# SPosition.net
KiCad netlist of a schematic drawn in EAGLE
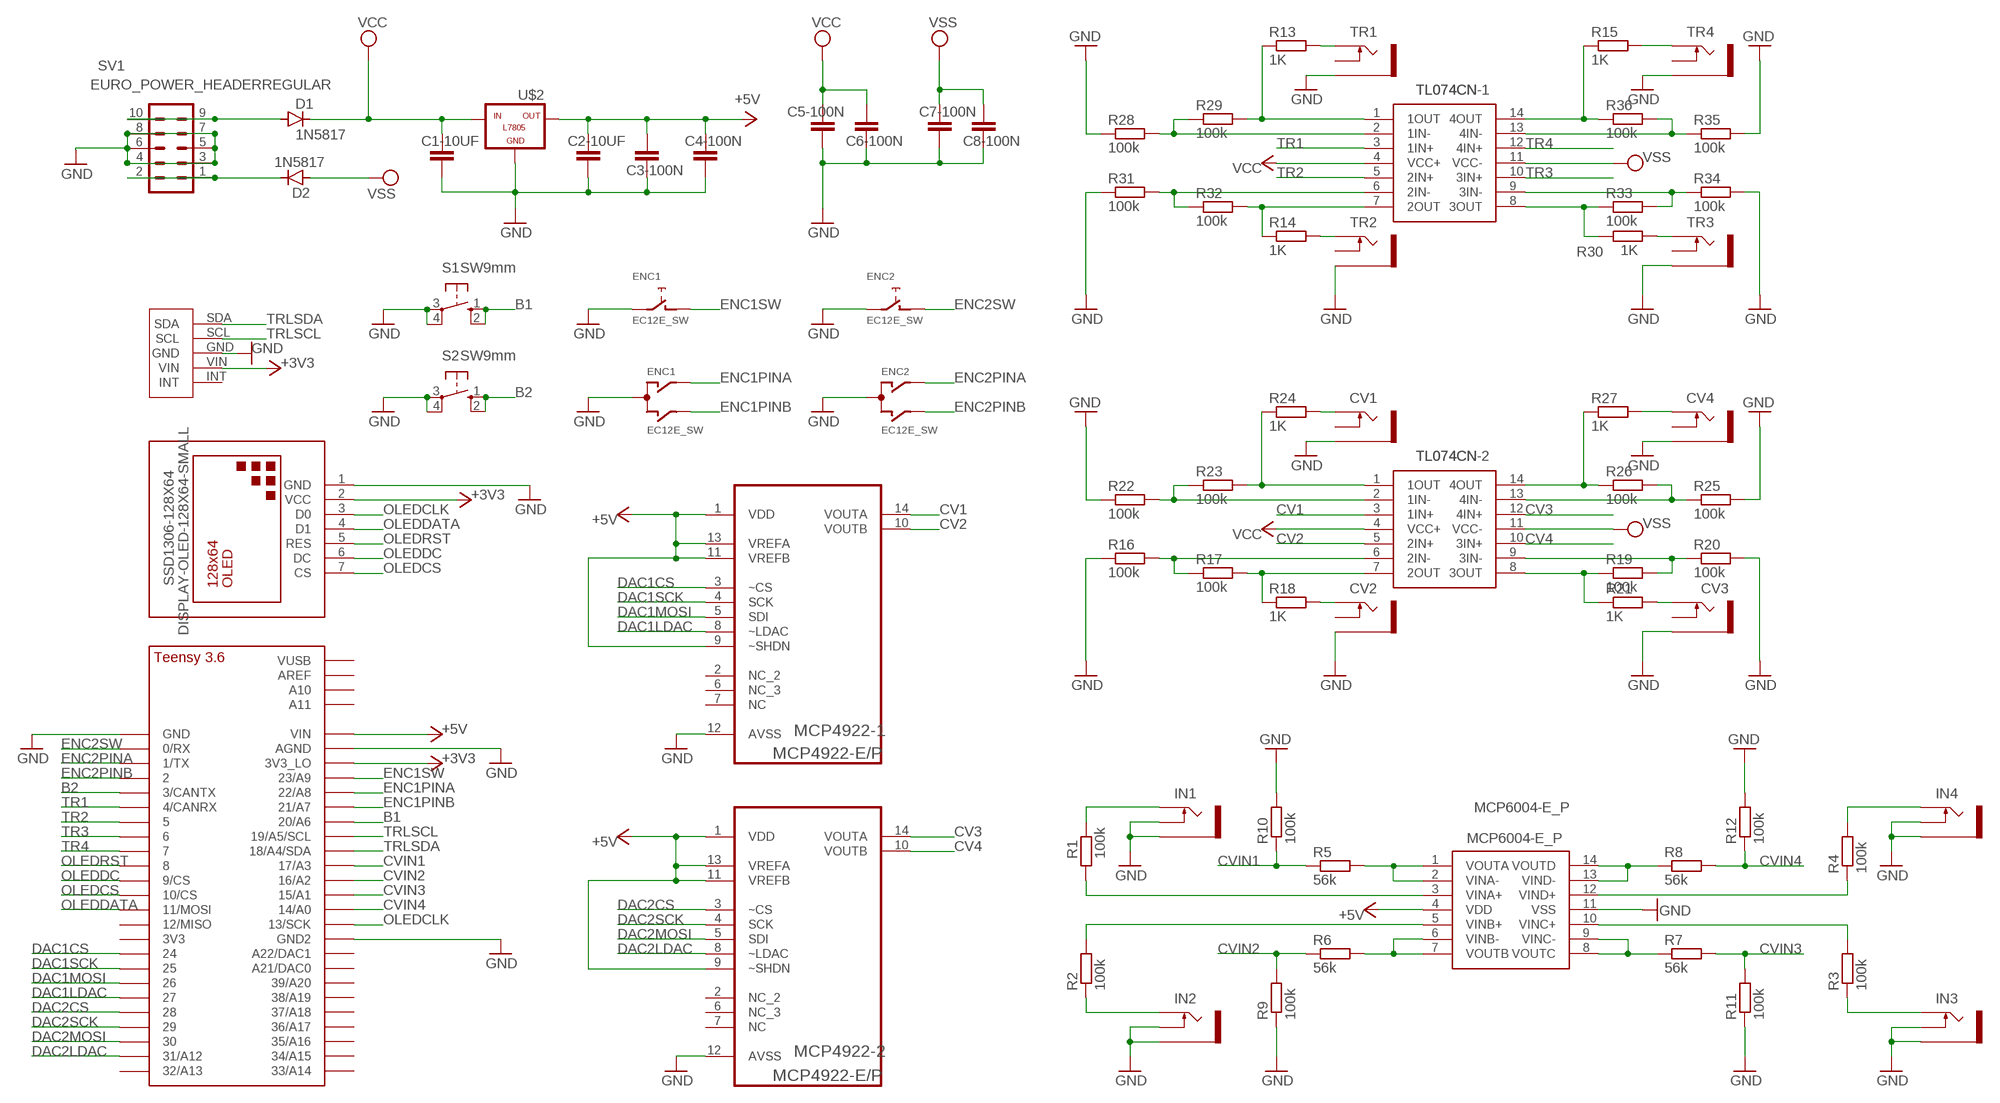
[diagram p0: schematic, sheet 1]

(export (version "E")
  (design (tool "Eeschema 10.0.6"))
  (components
    (comp (ref "C1-10UF")
      (value "10uF")
      (footprint "eagle-import:C0805")
      (libsource (lib "eagle-import") (part "C-EUC0805"))
    )
    (comp (ref "C2-10UF")
      (value "10uF")
      (footprint "eagle-import:C0805")
      (libsource (lib "eagle-import") (part "C-EUC0805"))
    )
    (comp (ref "C3-100N")
      (value "100n")
      (footprint "eagle-import:C0805")
      (libsource (lib "eagle-import") (part "C-EUC0805"))
    )
    (comp (ref "C4-100N")
      (value "100n")
      (footprint "eagle-import:C0805")
      (libsource (lib "eagle-import") (part "C-EUC0805"))
    )
    (comp (ref "C5-100N")
      (value "100n")
      (footprint "eagle-import:C0805")
      (libsource (lib "eagle-import") (part "C-EUC0805"))
    )
    (comp (ref "C6-100N")
      (value "100n")
      (footprint "eagle-import:C0805")
      (libsource (lib "eagle-import") (part "C-EUC0805"))
    )
    (comp (ref "C7-100N")
      (value "100n")
      (footprint "eagle-import:C0805")
      (libsource (lib "eagle-import") (part "C-EUC0805"))
    )
    (comp (ref "C8-100N")
      (value "100n")
      (footprint "eagle-import:C0805")
      (libsource (lib "eagle-import") (part "C-EUC0805"))
    )
    (comp (ref "CV1")
      (value "THONKICONNNEW")
      (footprint "eagle-import:WQP-PJ301M-12_JACK")
      (libsource (lib "eagle-import") (part "THONKICONNNEW"))
    )
    (comp (ref "CV2")
      (value "THONKICONNNEW")
      (footprint "eagle-import:WQP-PJ301M-12_JACK")
      (libsource (lib "eagle-import") (part "THONKICONNNEW"))
    )
    (comp (ref "CV3")
      (value "THONKICONNNEW")
      (footprint "eagle-import:WQP-PJ301M-12_JACK")
      (libsource (lib "eagle-import") (part "THONKICONNNEW"))
    )
    (comp (ref "CV4")
      (value "THONKICONNNEW")
      (footprint "eagle-import:WQP-PJ301M-12_JACK")
      (libsource (lib "eagle-import") (part "THONKICONNNEW"))
    )
    (comp (ref "D1")
      (value "1N5817")
      (footprint "eagle-import:DO41-10")
      (libsource (lib "eagle-import") (part "1N4004"))
    )
    (comp (ref "D2")
      (value "1N5817")
      (footprint "eagle-import:DO41-10")
      (libsource (lib "eagle-import") (part "1N4004"))
    )
    (comp (ref "ENC1")
      (value "EC12E_SW")
      (footprint "eagle-import:ALPS_EC12E_SW")
      (fields (field (name "MPN") "EC12E2424407"))
      (libsource (lib "eagle-import") (part "EC12E_SW"))
    )
    (comp (ref "ENC2")
      (value "EC12E_SW")
      (footprint "eagle-import:ALPS_EC12E_SW")
      (fields (field (name "MPN") "EC12E2424407"))
      (libsource (lib "eagle-import") (part "EC12E_SW"))
    )
    (comp (ref "IN1")
      (value "THONKICONNNEW")
      (footprint "eagle-import:WQP-PJ301M-12_JACK")
      (libsource (lib "eagle-import") (part "THONKICONNNEW"))
    )
    (comp (ref "IN2")
      (value "THONKICONNNEW")
      (footprint "eagle-import:WQP-PJ301M-12_JACK")
      (libsource (lib "eagle-import") (part "THONKICONNNEW"))
    )
    (comp (ref "IN3")
      (value "THONKICONNNEW")
      (footprint "eagle-import:WQP-PJ301M-12_JACK")
      (libsource (lib "eagle-import") (part "THONKICONNNEW"))
    )
    (comp (ref "IN4")
      (value "THONKICONNNEW")
      (footprint "eagle-import:WQP-PJ301M-12_JACK")
      (libsource (lib "eagle-import") (part "THONKICONNNEW"))
    )
    (comp (ref "MCP4922-1")
      (value "MCP4922-E/P")
      (footprint "eagle-import:DIP254P762X533-14")
      (fields (field (name "MF") "Microchip"))
      (libsource (lib "eagle-import") (part "MCP4922-E/P"))
    )
    (comp (ref "MCP4922-2")
      (value "MCP4922-E/P")
      (footprint "eagle-import:DIP254P762X533-14")
      (fields (field (name "MF") "Microchip"))
      (libsource (lib "eagle-import") (part "MCP4922-E/P"))
    )
    (comp (ref "MCP6004-E_P")
      (value "MCP6004-E_P")
      (footprint "eagle-import:DIP781W56P254L1918H533Q14N")
      (fields
        (field (name "MANUFACTURER_PART_NUMBER") "mcp6004-e/p")
        (field (name "MOUSER_PART_NUMBER") "579-MCP6004-E/P")
        (field (name "RS_PART_NUMBER") "7386178P")
      )
      (libsource (lib "eagle-import") (part "MCP6004-E_P"))
    )
    (comp (ref "R1")
      (value "100k")
      (footprint "eagle-import:R0805")
      (libsource (lib "eagle-import") (part "R-EU_R0805"))
    )
    (comp (ref "R2")
      (value "100k")
      (footprint "eagle-import:R0805")
      (libsource (lib "eagle-import") (part "R-EU_R0805"))
    )
    (comp (ref "R3")
      (value "100k")
      (footprint "eagle-import:R0805")
      (libsource (lib "eagle-import") (part "R-EU_R0805"))
    )
    (comp (ref "R4")
      (value "100k")
      (footprint "eagle-import:R0805")
      (libsource (lib "eagle-import") (part "R-EU_R0805"))
    )
    (comp (ref "R5")
      (value "56k")
      (footprint "eagle-import:R0805")
      (libsource (lib "eagle-import") (part "R-EU_R0805"))
    )
    (comp (ref "R6")
      (value "56k")
      (footprint "eagle-import:R0805")
      (libsource (lib "eagle-import") (part "R-EU_R0805"))
    )
    (comp (ref "R7")
      (value "56k")
      (footprint "eagle-import:R0805")
      (libsource (lib "eagle-import") (part "R-EU_R0805"))
    )
    (comp (ref "R8")
      (value "56k")
      (footprint "eagle-import:R0805")
      (libsource (lib "eagle-import") (part "R-EU_R0805"))
    )
    (comp (ref "R9")
      (value "100k")
      (footprint "eagle-import:R0805")
      (libsource (lib "eagle-import") (part "R-EU_R0805"))
    )
    (comp (ref "R10")
      (value "100k")
      (footprint "eagle-import:R0805")
      (libsource (lib "eagle-import") (part "R-EU_R0805"))
    )
    (comp (ref "R11")
      (value "100k")
      (footprint "eagle-import:R0805")
      (libsource (lib "eagle-import") (part "R-EU_R0805"))
    )
    (comp (ref "R12")
      (value "100k")
      (footprint "eagle-import:R0805")
      (libsource (lib "eagle-import") (part "R-EU_R0805"))
    )
    (comp (ref "R13")
      (value "1K")
      (footprint "eagle-import:R0805")
      (libsource (lib "eagle-import") (part "R-EU_R0805"))
    )
    (comp (ref "R14")
      (value "1K")
      (footprint "eagle-import:R0805")
      (libsource (lib "eagle-import") (part "R-EU_R0805"))
    )
    (comp (ref "R15")
      (value "1K")
      (footprint "eagle-import:R0805")
      (libsource (lib "eagle-import") (part "R-EU_R0805"))
    )
    (comp (ref "R16")
      (value "100k")
      (footprint "eagle-import:R0805")
      (libsource (lib "eagle-import") (part "R-EU_R0805"))
    )
    (comp (ref "R17")
      (value "100k")
      (footprint "eagle-import:R0805")
      (libsource (lib "eagle-import") (part "R-EU_R0805"))
    )
    (comp (ref "R18")
      (value "1K")
      (footprint "eagle-import:R0805")
      (libsource (lib "eagle-import") (part "R-EU_R0805"))
    )
    (comp (ref "R19")
      (value "100k")
      (footprint "eagle-import:R0805")
      (libsource (lib "eagle-import") (part "R-EU_R0805"))
    )
    (comp (ref "R20")
      (value "100k")
      (footprint "eagle-import:R0805")
      (libsource (lib "eagle-import") (part "R-EU_R0805"))
    )
    (comp (ref "R21")
      (value "1K")
      (footprint "eagle-import:R0805")
      (libsource (lib "eagle-import") (part "R-EU_R0805"))
    )
    (comp (ref "R22")
      (value "100k")
      (footprint "eagle-import:R0805")
      (libsource (lib "eagle-import") (part "R-EU_R0805"))
    )
    (comp (ref "R23")
      (value "100k")
      (footprint "eagle-import:R0805")
      (libsource (lib "eagle-import") (part "R-EU_R0805"))
    )
    (comp (ref "R24")
      (value "1K")
      (footprint "eagle-import:R0805")
      (libsource (lib "eagle-import") (part "R-EU_R0805"))
    )
    (comp (ref "R25")
      (value "100k")
      (footprint "eagle-import:R0805")
      (libsource (lib "eagle-import") (part "R-EU_R0805"))
    )
    (comp (ref "R26")
      (value "100k")
      (footprint "eagle-import:R0805")
      (libsource (lib "eagle-import") (part "R-EU_R0805"))
    )
    (comp (ref "R27")
      (value "1K")
      (footprint "eagle-import:R0805")
      (libsource (lib "eagle-import") (part "R-EU_R0805"))
    )
    (comp (ref "R28")
      (value "100k")
      (footprint "eagle-import:R0805")
      (libsource (lib "eagle-import") (part "R-EU_R0805"))
    )
    (comp (ref "R29")
      (value "100k")
      (footprint "eagle-import:R0805")
      (libsource (lib "eagle-import") (part "R-EU_R0805"))
    )
    (comp (ref "R30")
      (value "1K")
      (footprint "eagle-import:R0805")
      (libsource (lib "eagle-import") (part "R-EU_R0805"))
    )
    (comp (ref "R31")
      (value "100k")
      (footprint "eagle-import:R0805")
      (libsource (lib "eagle-import") (part "R-EU_R0805"))
    )
    (comp (ref "R32")
      (value "100k")
      (footprint "eagle-import:R0805")
      (libsource (lib "eagle-import") (part "R-EU_R0805"))
    )
    (comp (ref "R33")
      (value "100k")
      (footprint "eagle-import:R0805")
      (libsource (lib "eagle-import") (part "R-EU_R0805"))
    )
    (comp (ref "R34")
      (value "100k")
      (footprint "eagle-import:R0805")
      (libsource (lib "eagle-import") (part "R-EU_R0805"))
    )
    (comp (ref "R35")
      (value "100k")
      (footprint "eagle-import:R0805")
      (libsource (lib "eagle-import") (part "R-EU_R0805"))
    )
    (comp (ref "R36")
      (value "100k")
      (footprint "eagle-import:R0805")
      (libsource (lib "eagle-import") (part "R-EU_R0805"))
    )
    (comp (ref "S1")
      (value "SW9mm")
      (footprint "eagle-import:B3F-10XX")
      (fields (field (name "MPN") "B3F-1000"))
      (libsource (lib "eagle-import") (part "10-XX"))
    )
    (comp (ref "S2")
      (value "SW9mm")
      (footprint "eagle-import:B3F-10XX")
      (fields (field (name "MPN") "B3F-1000"))
      (libsource (lib "eagle-import") (part "10-XX"))
    )
    (comp (ref "SSD1306-128X64")
      (value "DISPLAY-OLED-128X64-SMALL")
      (footprint "eagle-import:DISPLAY-OLED-128X64-SMALL")
      (libsource (lib "eagle-import") (part "DISPLAY-OLED-128X64-SMALL"))
    )
    (comp (ref "SV1")
      (value "EURO_POWER_HEADERREGULAR")
      (footprint "eagle-import:EURO_POWER_HEADER")
      (libsource (lib "eagle-import") (part "EURO_POWER_HEADERREGULAR"))
    )
    (comp (ref "TL074CN-1")
      (value "TL074CN")
      (footprint "eagle-import:DIP794W53P254L1930H508Q14N")
      (fields (field (name "MOUSER_PART_NUMBER") "595-TL074CN") (field (name "RS_PART_NUMBER") "0302621P"))
      (libsource (lib "eagle-import") (part "TL074CN"))
    )
    (comp (ref "TL074CN-2")
      (value "TL074CN")
      (footprint "eagle-import:DIP794W53P254L1930H508Q14N")
      (fields (field (name "MOUSER_PART_NUMBER") "595-TL074CN") (field (name "RS_PART_NUMBER") "0302621P"))
      (libsource (lib "eagle-import") (part "TL074CN"))
    )
    (comp (ref "TR1")
      (value "THONKICONNNEW")
      (footprint "eagle-import:WQP-PJ301M-12_JACK")
      (libsource (lib "eagle-import") (part "THONKICONNNEW"))
    )
    (comp (ref "TR2")
      (value "THONKICONNNEW")
      (footprint "eagle-import:WQP-PJ301M-12_JACK")
      (libsource (lib "eagle-import") (part "THONKICONNNEW"))
    )
    (comp (ref "TR3")
      (value "THONKICONNNEW")
      (footprint "eagle-import:WQP-PJ301M-12_JACK")
      (libsource (lib "eagle-import") (part "THONKICONNNEW"))
    )
    (comp (ref "TR4")
      (value "THONKICONNNEW")
      (footprint "eagle-import:WQP-PJ301M-12_JACK")
      (libsource (lib "eagle-import") (part "THONKICONNNEW"))
    )
    (comp (ref "U$1")
      (value "TEENSY_3.5/3.6_BASIC")
      (footprint "eagle-import:TEENSY_3.5_3.6_BASIC")
      (libsource (lib "eagle-import") (part "TEENSY_3.5/3.6_BASIC"))
    )
    (comp (ref "U$2")
      (value "-L7805")
      (footprint "eagle-import:L7805")
      (libsource (lib "eagle-import") (part "-L7805"))
    )
    (comp (ref "U$4")
      (value "SPREV5")
      (footprint "eagle-import:SPREV5")
      (libsource (lib "eagle-import") (part "SPREV5"))
    )
  )
  (nets
    (net (code "1") (name "+3V3") (class "Default")
      (node (ref "SSD1306-128X64") (pin "2") (pinfunction "VCC_2") (pintype "power_in"))
      (node (ref "U$1") (pin "3V3_LO") (pinfunction "3V3_LO_3V3_LO") (pintype "bidirectional"))
      (node (ref "U$4") (pin "VIN") (pinfunction "VIN_VIN") (pintype "bidirectional"))
    )
    (net (code "2") (name "+5V") (class "Default")
      (node (ref "C2-10UF") (pin "1") (pinfunction "1_1") (pintype "passive"))
      (node (ref "C3-100N") (pin "1") (pinfunction "1_1") (pintype "passive"))
      (node (ref "C4-100N") (pin "1") (pinfunction "1_1") (pintype "passive"))
      (node (ref "MCP4922-1") (pin "1") (pinfunction "VDD_1") (pintype "power_in"))
      (node (ref "MCP4922-1") (pin "11") (pinfunction "VREFB_11") (pintype "input"))
      (node (ref "MCP4922-1") (pin "13") (pinfunction "VREFA_13") (pintype "input"))
      (node (ref "MCP4922-1") (pin "9") (pinfunction "~{SHDN}_9") (pintype "input"))
      (node (ref "MCP4922-2") (pin "1") (pinfunction "VDD_1") (pintype "power_in"))
      (node (ref "MCP4922-2") (pin "11") (pinfunction "VREFB_11") (pintype "input"))
      (node (ref "MCP4922-2") (pin "13") (pinfunction "VREFA_13") (pintype "input"))
      (node (ref "MCP4922-2") (pin "9") (pinfunction "~{SHDN}_9") (pintype "input"))
      (node (ref "MCP6004-E_P") (pin "4") (pinfunction "VDD_4") (pintype "power_in"))
      (node (ref "U$1") (pin "VIN") (pinfunction "VIN_VIN") (pintype "bidirectional"))
      (node (ref "U$2") (pin "OUT") (pinfunction "OUT_OUT") (pintype "passive"))
    )
    (net (code "3") (name "/B1") (class "Default")
      (node (ref "S1") (pin "1") (pinfunction "S_1") (pintype "passive"))
      (node (ref "S1") (pin "2") (pinfunction "S1_2") (pintype "passive"))
      (node (ref "U$1") (pin "20/A6") (pinfunction "20/A6_20/A6") (pintype "bidirectional"))
    )
    (net (code "4") (name "/B2") (class "Default")
      (node (ref "S2") (pin "1") (pinfunction "S_1") (pintype "passive"))
      (node (ref "S2") (pin "2") (pinfunction "S1_2") (pintype "passive"))
      (node (ref "U$1") (pin "3/CANTX") (pinfunction "3/CANTX_3/CANTX") (pintype "bidirectional"))
    )
    (net (code "5") (name "/CV1") (class "Default")
      (node (ref "MCP4922-1") (pin "14") (pinfunction "VOUTA_14") (pintype "output"))
      (node (ref "TL074CN-2") (pin "3") (pinfunction "1IN+_3") (pintype "input"))
    )
    (net (code "6") (name "/CV2") (class "Default")
      (node (ref "MCP4922-1") (pin "10") (pinfunction "VOUTB_10") (pintype "output"))
      (node (ref "TL074CN-2") (pin "5") (pinfunction "2IN+_5") (pintype "input"))
    )
    (net (code "7") (name "/CV3") (class "Default")
      (node (ref "MCP4922-2") (pin "14") (pinfunction "VOUTA_14") (pintype "output"))
      (node (ref "TL074CN-2") (pin "12") (pinfunction "4IN+_12") (pintype "input"))
    )
    (net (code "8") (name "/CV4") (class "Default")
      (node (ref "MCP4922-2") (pin "10") (pinfunction "VOUTB_10") (pintype "output"))
      (node (ref "TL074CN-2") (pin "10") (pinfunction "3IN+_10") (pintype "input"))
    )
    (net (code "9") (name "/CVIN1") (class "Default")
      (node (ref "R10") (pin "1") (pinfunction "1_1") (pintype "passive"))
      (node (ref "R5") (pin "1") (pinfunction "1_1") (pintype "passive"))
      (node (ref "U$1") (pin "17/A3") (pinfunction "17/A3_17/A3") (pintype "bidirectional"))
    )
    (net (code "10") (name "/CVIN2") (class "Default")
      (node (ref "R6") (pin "1") (pinfunction "1_1") (pintype "passive"))
      (node (ref "R9") (pin "2") (pinfunction "2_2") (pintype "passive"))
      (node (ref "U$1") (pin "16/A2") (pinfunction "16/A2_16/A2") (pintype "bidirectional"))
    )
    (net (code "11") (name "/CVIN3") (class "Default")
      (node (ref "R11") (pin "2") (pinfunction "2_2") (pintype "passive"))
      (node (ref "R7") (pin "2") (pinfunction "2_2") (pintype "passive"))
      (node (ref "U$1") (pin "15/A1") (pinfunction "15/A1_15/A1") (pintype "bidirectional"))
    )
    (net (code "12") (name "/CVIN4") (class "Default")
      (node (ref "R12") (pin "1") (pinfunction "1_1") (pintype "passive"))
      (node (ref "R8") (pin "2") (pinfunction "2_2") (pintype "passive"))
      (node (ref "U$1") (pin "14/A0") (pinfunction "14/A0_14/A0") (pintype "bidirectional"))
    )
    (net (code "13") (name "/DAC1CS") (class "Default")
      (node (ref "MCP4922-1") (pin "3") (pinfunction "~{CS}_3") (pintype "input"))
      (node (ref "U$1") (pin "24") (pinfunction "24_24") (pintype "bidirectional"))
    )
    (net (code "14") (name "/DAC1LDAC") (class "Default")
      (node (ref "MCP4922-1") (pin "8") (pinfunction "~{LDAC}_8") (pintype "input"))
      (node (ref "U$1") (pin "27") (pinfunction "27_27") (pintype "bidirectional"))
    )
    (net (code "15") (name "/DAC1MOSI") (class "Default")
      (node (ref "MCP4922-1") (pin "5") (pinfunction "SDI_5") (pintype "input"))
      (node (ref "U$1") (pin "26") (pinfunction "26_26") (pintype "bidirectional"))
    )
    (net (code "16") (name "/DAC1SCK") (class "Default")
      (node (ref "MCP4922-1") (pin "4") (pinfunction "SCK_4") (pintype "input"))
      (node (ref "U$1") (pin "25") (pinfunction "25_25") (pintype "bidirectional"))
    )
    (net (code "17") (name "/DAC2CS") (class "Default")
      (node (ref "MCP4922-2") (pin "3") (pinfunction "~{CS}_3") (pintype "input"))
      (node (ref "U$1") (pin "28") (pinfunction "28_28") (pintype "bidirectional"))
    )
    (net (code "18") (name "/DAC2LDAC") (class "Default")
      (node (ref "MCP4922-2") (pin "8") (pinfunction "~{LDAC}_8") (pintype "input"))
      (node (ref "U$1") (pin "31/A12") (pinfunction "31/A12_31/A12") (pintype "bidirectional"))
    )
    (net (code "19") (name "/DAC2MOSI") (class "Default")
      (node (ref "MCP4922-2") (pin "5") (pinfunction "SDI_5") (pintype "input"))
      (node (ref "U$1") (pin "30") (pinfunction "30_30") (pintype "bidirectional"))
    )
    (net (code "20") (name "/DAC2SCK") (class "Default")
      (node (ref "MCP4922-2") (pin "4") (pinfunction "SCK_4") (pintype "input"))
      (node (ref "U$1") (pin "29") (pinfunction "29_29") (pintype "bidirectional"))
    )
    (net (code "21") (name "/ENC1PINA") (class "Default")
      (node (ref "ENC1") (pin "A") (pinfunction "A_A") (pintype "passive"))
      (node (ref "U$1") (pin "22/A8") (pinfunction "22/A8_22/A8") (pintype "bidirectional"))
    )
    (net (code "22") (name "/ENC1PINB") (class "Default")
      (node (ref "ENC1") (pin "B") (pinfunction "B_B") (pintype "passive"))
      (node (ref "U$1") (pin "21/A7") (pinfunction "21/A7_21/A7") (pintype "bidirectional"))
    )
    (net (code "23") (name "/ENC1SW") (class "Default")
      (node (ref "ENC1") (pin "D") (pinfunction "1_D") (pintype "passive"))
      (node (ref "U$1") (pin "23/A9") (pinfunction "23/A9_23/A9") (pintype "bidirectional"))
    )
    (net (code "24") (name "/ENC2PINA") (class "Default")
      (node (ref "ENC2") (pin "A") (pinfunction "A_A") (pintype "passive"))
      (node (ref "U$1") (pin "1/TX") (pinfunction "1/TX_1/TX") (pintype "bidirectional"))
    )
    (net (code "25") (name "/ENC2PINB") (class "Default")
      (node (ref "ENC2") (pin "B") (pinfunction "B_B") (pintype "passive"))
      (node (ref "U$1") (pin "2") (pinfunction "2_2") (pintype "bidirectional"))
    )
    (net (code "26") (name "/ENC2SW") (class "Default")
      (node (ref "ENC2") (pin "D") (pinfunction "1_D") (pintype "passive"))
      (node (ref "U$1") (pin "0/RX") (pinfunction "0/RX_0/RX") (pintype "bidirectional"))
    )
    (net (code "27") (name "/OLEDCLK") (class "Default")
      (node (ref "SSD1306-128X64") (pin "3") (pinfunction "D0_3") (pintype "bidirectional"))
      (node (ref "U$1") (pin "13/SCK") (pinfunction "13/SCK_13/SCK") (pintype "bidirectional"))
    )
    (net (code "28") (name "/OLEDCS") (class "Default")
      (node (ref "SSD1306-128X64") (pin "7") (pinfunction "CS_7") (pintype "bidirectional"))
      (node (ref "U$1") (pin "10/CS") (pinfunction "10/CS_10/CS") (pintype "bidirectional"))
    )
    (net (code "29") (name "/OLEDDATA") (class "Default")
      (node (ref "SSD1306-128X64") (pin "4") (pinfunction "D1_4") (pintype "bidirectional"))
      (node (ref "U$1") (pin "11/MOSI") (pinfunction "11/MOSI_11/MOSI") (pintype "bidirectional"))
    )
    (net (code "30") (name "/OLEDDC") (class "Default")
      (node (ref "SSD1306-128X64") (pin "6") (pinfunction "DC_6") (pintype "bidirectional"))
      (node (ref "U$1") (pin "9/CS") (pinfunction "9/CS_9/CS") (pintype "bidirectional"))
    )
    (net (code "31") (name "/OLEDRST") (class "Default")
      (node (ref "SSD1306-128X64") (pin "5") (pinfunction "RES_5") (pintype "bidirectional"))
      (node (ref "U$1") (pin "8") (pinfunction "8_8") (pintype "bidirectional"))
    )
    (net (code "32") (name "/TR1") (class "Default")
      (node (ref "TL074CN-1") (pin "3") (pinfunction "1IN+_3") (pintype "input"))
      (node (ref "U$1") (pin "4/CANRX") (pinfunction "4/CANRX_4/CANRX") (pintype "bidirectional"))
    )
    (net (code "33") (name "/TR2") (class "Default")
      (node (ref "TL074CN-1") (pin "5") (pinfunction "2IN+_5") (pintype "input"))
      (node (ref "U$1") (pin "5") (pinfunction "5_5") (pintype "bidirectional"))
    )
    (net (code "34") (name "/TR3") (class "Default")
      (node (ref "TL074CN-1") (pin "10") (pinfunction "3IN+_10") (pintype "input"))
      (node (ref "U$1") (pin "6") (pinfunction "6_6") (pintype "bidirectional"))
    )
    (net (code "35") (name "/TR4") (class "Default")
      (node (ref "TL074CN-1") (pin "12") (pinfunction "4IN+_12") (pintype "input"))
      (node (ref "U$1") (pin "7") (pinfunction "7_7") (pintype "bidirectional"))
    )
    (net (code "36") (name "/TRLSCL") (class "Default")
      (node (ref "U$1") (pin "19/A5/SCL") (pinfunction "19/A5/SCL_19/A5/SCL") (pintype "bidirectional"))
      (node (ref "U$4") (pin "SCL") (pinfunction "SCL_SCL") (pintype "bidirectional"))
    )
    (net (code "37") (name "/TRLSDA") (class "Default")
      (node (ref "U$1") (pin "18/A4/SDA") (pinfunction "18/A4/SDA_18/A4/SDA") (pintype "bidirectional"))
      (node (ref "U$4") (pin "SDA") (pinfunction "SDA_SDA") (pintype "bidirectional"))
    )
    (net (code "38") (name "GND") (class "Default")
      (node (ref "C1-10UF") (pin "2") (pinfunction "2_2") (pintype "passive"))
      (node (ref "C2-10UF") (pin "2") (pinfunction "2_2") (pintype "passive"))
      (node (ref "C3-100N") (pin "2") (pinfunction "2_2") (pintype "passive"))
      (node (ref "C4-100N") (pin "2") (pinfunction "2_2") (pintype "passive"))
      (node (ref "C5-100N") (pin "2") (pinfunction "2_2") (pintype "passive"))
      (node (ref "C6-100N") (pin "2") (pinfunction "2_2") (pintype "passive"))
      (node (ref "C7-100N") (pin "2") (pinfunction "2_2") (pintype "passive"))
      (node (ref "C8-100N") (pin "2") (pinfunction "2_2") (pintype "passive"))
      (node (ref "CV1") (pin "P$3_SLEEVE") (pinfunction "SLEEVE_P$3_SLEEVE") (pintype "passive"))
      (node (ref "CV2") (pin "P$3_SLEEVE") (pinfunction "SLEEVE_P$3_SLEEVE") (pintype "passive"))
      (node (ref "CV3") (pin "P$3_SLEEVE") (pinfunction "SLEEVE_P$3_SLEEVE") (pintype "passive"))
      (node (ref "CV4") (pin "P$3_SLEEVE") (pinfunction "SLEEVE_P$3_SLEEVE") (pintype "passive"))
      (node (ref "ENC1") (pin "C") (pinfunction "C_C") (pintype "passive"))
      (node (ref "ENC1") (pin "E") (pinfunction "2_E") (pintype "passive"))
      (node (ref "ENC2") (pin "C") (pinfunction "C_C") (pintype "passive"))
      (node (ref "ENC2") (pin "E") (pinfunction "2_E") (pintype "passive"))
      (node (ref "IN1") (pin "P$2_SWITCH") (pinfunction "SWITCH_P$2_SWITCH") (pintype "passive"))
      (node (ref "IN1") (pin "P$3_SLEEVE") (pinfunction "SLEEVE_P$3_SLEEVE") (pintype "passive"))
      (node (ref "IN2") (pin "P$2_SWITCH") (pinfunction "SWITCH_P$2_SWITCH") (pintype "passive"))
      (node (ref "IN2") (pin "P$3_SLEEVE") (pinfunction "SLEEVE_P$3_SLEEVE") (pintype "passive"))
      (node (ref "IN3") (pin "P$2_SWITCH") (pinfunction "SWITCH_P$2_SWITCH") (pintype "passive"))
      (node (ref "IN3") (pin "P$3_SLEEVE") (pinfunction "SLEEVE_P$3_SLEEVE") (pintype "passive"))
      (node (ref "IN4") (pin "P$2_SWITCH") (pinfunction "SWITCH_P$2_SWITCH") (pintype "passive"))
      (node (ref "IN4") (pin "P$3_SLEEVE") (pinfunction "SLEEVE_P$3_SLEEVE") (pintype "passive"))
      (node (ref "MCP4922-1") (pin "12") (pinfunction "AVSS_12") (pintype "power_in"))
      (node (ref "MCP4922-2") (pin "12") (pinfunction "AVSS_12") (pintype "power_in"))
      (node (ref "MCP6004-E_P") (pin "11") (pinfunction "VSS_11") (pintype "power_in"))
      (node (ref "R10") (pin "2") (pinfunction "2_2") (pintype "passive"))
      (node (ref "R11") (pin "1") (pinfunction "1_1") (pintype "passive"))
      (node (ref "R12") (pin "2") (pinfunction "2_2") (pintype "passive"))
      (node (ref "R16") (pin "1") (pinfunction "1_1") (pintype "passive"))
      (node (ref "R20") (pin "2") (pinfunction "2_2") (pintype "passive"))
      (node (ref "R22") (pin "1") (pinfunction "1_1") (pintype "passive"))
      (node (ref "R25") (pin "2") (pinfunction "2_2") (pintype "passive"))
      (node (ref "R28") (pin "1") (pinfunction "1_1") (pintype "passive"))
      (node (ref "R31") (pin "1") (pinfunction "1_1") (pintype "passive"))
      (node (ref "R34") (pin "2") (pinfunction "2_2") (pintype "passive"))
      (node (ref "R35") (pin "2") (pinfunction "2_2") (pintype "passive"))
      (node (ref "R9") (pin "1") (pinfunction "1_1") (pintype "passive"))
      (node (ref "S1") (pin "3") (pinfunction "P_3") (pintype "passive"))
      (node (ref "S1") (pin "4") (pinfunction "P1_4") (pintype "passive"))
      (node (ref "S2") (pin "3") (pinfunction "P_3") (pintype "passive"))
      (node (ref "S2") (pin "4") (pinfunction "P1_4") (pintype "passive"))
      (node (ref "SSD1306-128X64") (pin "1") (pinfunction "GND_1") (pintype "power_in"))
      (node (ref "SV1") (pin "3") (pinfunction "3_3") (pintype "passive"))
      (node (ref "SV1") (pin "4") (pinfunction "4_4") (pintype "passive"))
      (node (ref "SV1") (pin "5") (pinfunction "5_5") (pintype "passive"))
      (node (ref "SV1") (pin "6") (pinfunction "6_6") (pintype "passive"))
      (node (ref "SV1") (pin "7") (pinfunction "7_7") (pintype "passive"))
      (node (ref "SV1") (pin "8") (pinfunction "8_8") (pintype "passive"))
      (node (ref "TR1") (pin "P$3_SLEEVE") (pinfunction "SLEEVE_P$3_SLEEVE") (pintype "passive"))
      (node (ref "TR2") (pin "P$3_SLEEVE") (pinfunction "SLEEVE_P$3_SLEEVE") (pintype "passive"))
      (node (ref "TR3") (pin "P$3_SLEEVE") (pinfunction "SLEEVE_P$3_SLEEVE") (pintype "passive"))
      (node (ref "TR4") (pin "P$3_SLEEVE") (pinfunction "SLEEVE_P$3_SLEEVE") (pintype "passive"))
      (node (ref "U$1") (pin "AGND") (pinfunction "AGND_AGND") (pintype "bidirectional"))
      (node (ref "U$1") (pin "GND") (pinfunction "GND_GND") (pintype "bidirectional"))
      (node (ref "U$1") (pin "GND2") (pinfunction "GND2_GND2") (pintype "bidirectional"))
      (node (ref "U$2") (pin "GND") (pinfunction "GND_GND") (pintype "input"))
      (node (ref "U$4") (pin "GND") (pinfunction "GND_GND") (pintype "bidirectional"))
    )
    (net (code "39") (name "Net-(CV1-TIP)") (class "Default")
      (node (ref "CV1") (pin "P$1_TIP") (pinfunction "TIP_P$1_TIP") (pintype "passive"))
      (node (ref "R24") (pin "2") (pinfunction "2_2") (pintype "passive"))
    )
    (net (code "40") (name "Net-(CV2-TIP)") (class "Default")
      (node (ref "CV2") (pin "P$1_TIP") (pinfunction "TIP_P$1_TIP") (pintype "passive"))
      (node (ref "R18") (pin "2") (pinfunction "2_2") (pintype "passive"))
    )
    (net (code "41") (name "Net-(CV3-TIP)") (class "Default")
      (node (ref "CV3") (pin "P$1_TIP") (pinfunction "TIP_P$1_TIP") (pintype "passive"))
      (node (ref "R21") (pin "2") (pinfunction "2_2") (pintype "passive"))
    )
    (net (code "42") (name "Net-(CV4-TIP)") (class "Default")
      (node (ref "CV4") (pin "P$1_TIP") (pinfunction "TIP_P$1_TIP") (pintype "passive"))
      (node (ref "R27") (pin "2") (pinfunction "2_2") (pintype "passive"))
    )
    (net (code "43") (name "Net-(D1-PadA)") (class "Default")
      (node (ref "D1") (pin "A") (pinfunction "A_A") (pintype "passive"))
      (node (ref "SV1") (pin "10") (pinfunction "10_10") (pintype "passive"))
      (node (ref "SV1") (pin "9") (pinfunction "9_9") (pintype "passive"))
    )
    (net (code "44") (name "Net-(D2-PadC)") (class "Default")
      (node (ref "D2") (pin "C") (pinfunction "C_C") (pintype "passive"))
      (node (ref "SV1") (pin "1") (pinfunction "1_1") (pintype "passive"))
      (node (ref "SV1") (pin "2") (pinfunction "2_2") (pintype "passive"))
    )
    (net (code "45") (name "Net-(IN1-TIP)") (class "Default")
      (node (ref "IN1") (pin "P$1_TIP") (pinfunction "TIP_P$1_TIP") (pintype "passive"))
      (node (ref "R1") (pin "2") (pinfunction "2_2") (pintype "passive"))
    )
    (net (code "46") (name "Net-(IN2-TIP)") (class "Default")
      (node (ref "IN2") (pin "P$1_TIP") (pinfunction "TIP_P$1_TIP") (pintype "passive"))
      (node (ref "R2") (pin "1") (pinfunction "1_1") (pintype "passive"))
    )
    (net (code "47") (name "Net-(IN3-TIP)") (class "Default")
      (node (ref "IN3") (pin "P$1_TIP") (pinfunction "TIP_P$1_TIP") (pintype "passive"))
      (node (ref "R3") (pin "1") (pinfunction "1_1") (pintype "passive"))
    )
    (net (code "48") (name "Net-(IN4-TIP)") (class "Default")
      (node (ref "IN4") (pin "P$1_TIP") (pinfunction "TIP_P$1_TIP") (pintype "passive"))
      (node (ref "R4") (pin "2") (pinfunction "2_2") (pintype "passive"))
    )
    (net (code "49") (name "Net-(MCP6004-E_P-VINA+)") (class "Default")
      (node (ref "MCP6004-E_P") (pin "3") (pinfunction "VINA+_3") (pintype "input"))
      (node (ref "R1") (pin "1") (pinfunction "1_1") (pintype "passive"))
    )
    (net (code "50") (name "Net-(MCP6004-E_P-VINA-)") (class "Default")
      (node (ref "MCP6004-E_P") (pin "1") (pinfunction "VOUTA_1") (pintype "output"))
      (node (ref "MCP6004-E_P") (pin "2") (pinfunction "VINA-_2") (pintype "input"))
      (node (ref "R5") (pin "2") (pinfunction "2_2") (pintype "passive"))
    )
    (net (code "51") (name "Net-(MCP6004-E_P-VINB+)") (class "Default")
      (node (ref "MCP6004-E_P") (pin "5") (pinfunction "VINB+_5") (pintype "input"))
      (node (ref "R2") (pin "2") (pinfunction "2_2") (pintype "passive"))
    )
    (net (code "52") (name "Net-(MCP6004-E_P-VINB-)") (class "Default")
      (node (ref "MCP6004-E_P") (pin "6") (pinfunction "VINB-_6") (pintype "input"))
      (node (ref "MCP6004-E_P") (pin "7") (pinfunction "VOUTB_7") (pintype "output"))
      (node (ref "R6") (pin "2") (pinfunction "2_2") (pintype "passive"))
    )
    (net (code "53") (name "Net-(MCP6004-E_P-VINC+)") (class "Default")
      (node (ref "MCP6004-E_P") (pin "10") (pinfunction "VINC+_10") (pintype "input"))
      (node (ref "R3") (pin "2") (pinfunction "2_2") (pintype "passive"))
    )
    (net (code "54") (name "Net-(MCP6004-E_P-VINC-)") (class "Default")
      (node (ref "MCP6004-E_P") (pin "8") (pinfunction "VOUTC_8") (pintype "output"))
      (node (ref "MCP6004-E_P") (pin "9") (pinfunction "VINC-_9") (pintype "input"))
      (node (ref "R7") (pin "1") (pinfunction "1_1") (pintype "passive"))
    )
    (net (code "55") (name "Net-(MCP6004-E_P-VIND+)") (class "Default")
      (node (ref "MCP6004-E_P") (pin "12") (pinfunction "VIND+_12") (pintype "input"))
      (node (ref "R4") (pin "1") (pinfunction "1_1") (pintype "passive"))
    )
    (net (code "56") (name "Net-(MCP6004-E_P-VIND-)") (class "Default")
      (node (ref "MCP6004-E_P") (pin "13") (pinfunction "VIND-_13") (pintype "input"))
      (node (ref "MCP6004-E_P") (pin "14") (pinfunction "VOUTD_14") (pintype "output"))
      (node (ref "R8") (pin "1") (pinfunction "1_1") (pintype "passive"))
    )
    (net (code "57") (name "Net-(TL074CN-1-1IN-)") (class "Default")
      (node (ref "R28") (pin "2") (pinfunction "2_2") (pintype "passive"))
      (node (ref "R29") (pin "1") (pinfunction "1_1") (pintype "passive"))
      (node (ref "TL074CN-1") (pin "2") (pinfunction "1IN-_2") (pintype "input"))
    )
    (net (code "58") (name "Net-(TL074CN-1-1OUT)") (class "Default")
      (node (ref "R13") (pin "1") (pinfunction "1_1") (pintype "passive"))
      (node (ref "R29") (pin "2") (pinfunction "2_2") (pintype "passive"))
      (node (ref "TL074CN-1") (pin "1") (pinfunction "1OUT_1") (pintype "output"))
    )
    (net (code "59") (name "Net-(TL074CN-1-2IN-)") (class "Default")
      (node (ref "R31") (pin "2") (pinfunction "2_2") (pintype "passive"))
      (node (ref "R32") (pin "1") (pinfunction "1_1") (pintype "passive"))
      (node (ref "TL074CN-1") (pin "6") (pinfunction "2IN-_6") (pintype "input"))
    )
    (net (code "60") (name "Net-(TL074CN-1-2OUT)") (class "Default")
      (node (ref "R14") (pin "1") (pinfunction "1_1") (pintype "passive"))
      (node (ref "R32") (pin "2") (pinfunction "2_2") (pintype "passive"))
      (node (ref "TL074CN-1") (pin "7") (pinfunction "2OUT_7") (pintype "output"))
    )
    (net (code "61") (name "Net-(TL074CN-1-3IN-)") (class "Default")
      (node (ref "R33") (pin "2") (pinfunction "2_2") (pintype "passive"))
      (node (ref "R34") (pin "1") (pinfunction "1_1") (pintype "passive"))
      (node (ref "TL074CN-1") (pin "9") (pinfunction "3IN-_9") (pintype "input"))
    )
    (net (code "62") (name "Net-(TL074CN-1-3OUT)") (class "Default")
      (node (ref "R30") (pin "1") (pinfunction "1_1") (pintype "passive"))
      (node (ref "R33") (pin "1") (pinfunction "1_1") (pintype "passive"))
      (node (ref "TL074CN-1") (pin "8") (pinfunction "3OUT_8") (pintype "output"))
    )
    (net (code "63") (name "Net-(TL074CN-1-4IN-)") (class "Default")
      (node (ref "R35") (pin "1") (pinfunction "1_1") (pintype "passive"))
      (node (ref "R36") (pin "2") (pinfunction "2_2") (pintype "passive"))
      (node (ref "TL074CN-1") (pin "13") (pinfunction "4IN-_13") (pintype "input"))
    )
    (net (code "64") (name "Net-(TL074CN-1-4OUT)") (class "Default")
      (node (ref "R15") (pin "1") (pinfunction "1_1") (pintype "passive"))
      (node (ref "R36") (pin "1") (pinfunction "1_1") (pintype "passive"))
      (node (ref "TL074CN-1") (pin "14") (pinfunction "4OUT_14") (pintype "output"))
    )
    (net (code "65") (name "Net-(TL074CN-2-1IN-)") (class "Default")
      (node (ref "R22") (pin "2") (pinfunction "2_2") (pintype "passive"))
      (node (ref "R23") (pin "1") (pinfunction "1_1") (pintype "passive"))
      (node (ref "TL074CN-2") (pin "2") (pinfunction "1IN-_2") (pintype "input"))
    )
    (net (code "66") (name "Net-(TL074CN-2-1OUT)") (class "Default")
      (node (ref "R23") (pin "2") (pinfunction "2_2") (pintype "passive"))
      (node (ref "R24") (pin "1") (pinfunction "1_1") (pintype "passive"))
      (node (ref "TL074CN-2") (pin "1") (pinfunction "1OUT_1") (pintype "output"))
    )
    (net (code "67") (name "Net-(TL074CN-2-2IN-)") (class "Default")
      (node (ref "R16") (pin "2") (pinfunction "2_2") (pintype "passive"))
      (node (ref "R17") (pin "1") (pinfunction "1_1") (pintype "passive"))
      (node (ref "TL074CN-2") (pin "6") (pinfunction "2IN-_6") (pintype "input"))
    )
    (net (code "68") (name "Net-(TL074CN-2-2OUT)") (class "Default")
      (node (ref "R17") (pin "2") (pinfunction "2_2") (pintype "passive"))
      (node (ref "R18") (pin "1") (pinfunction "1_1") (pintype "passive"))
      (node (ref "TL074CN-2") (pin "7") (pinfunction "2OUT_7") (pintype "output"))
    )
    (net (code "69") (name "Net-(TL074CN-2-3IN-)") (class "Default")
      (node (ref "R19") (pin "2") (pinfunction "2_2") (pintype "passive"))
      (node (ref "R20") (pin "1") (pinfunction "1_1") (pintype "passive"))
      (node (ref "TL074CN-2") (pin "9") (pinfunction "3IN-_9") (pintype "input"))
    )
    (net (code "70") (name "Net-(TL074CN-2-3OUT)") (class "Default")
      (node (ref "R19") (pin "1") (pinfunction "1_1") (pintype "passive"))
      (node (ref "R21") (pin "1") (pinfunction "1_1") (pintype "passive"))
      (node (ref "TL074CN-2") (pin "8") (pinfunction "3OUT_8") (pintype "output"))
    )
    (net (code "71") (name "Net-(TL074CN-2-4IN-)") (class "Default")
      (node (ref "R25") (pin "1") (pinfunction "1_1") (pintype "passive"))
      (node (ref "R26") (pin "2") (pinfunction "2_2") (pintype "passive"))
      (node (ref "TL074CN-2") (pin "13") (pinfunction "4IN-_13") (pintype "input"))
    )
    (net (code "72") (name "Net-(TL074CN-2-4OUT)") (class "Default")
      (node (ref "R26") (pin "1") (pinfunction "1_1") (pintype "passive"))
      (node (ref "R27") (pin "1") (pinfunction "1_1") (pintype "passive"))
      (node (ref "TL074CN-2") (pin "14") (pinfunction "4OUT_14") (pintype "output"))
    )
    (net (code "73") (name "Net-(TR1-TIP)") (class "Default")
      (node (ref "R13") (pin "2") (pinfunction "2_2") (pintype "passive"))
      (node (ref "TR1") (pin "P$1_TIP") (pinfunction "TIP_P$1_TIP") (pintype "passive"))
    )
    (net (code "74") (name "Net-(TR2-TIP)") (class "Default")
      (node (ref "R14") (pin "2") (pinfunction "2_2") (pintype "passive"))
      (node (ref "TR2") (pin "P$1_TIP") (pinfunction "TIP_P$1_TIP") (pintype "passive"))
    )
    (net (code "75") (name "Net-(TR3-TIP)") (class "Default")
      (node (ref "R30") (pin "2") (pinfunction "2_2") (pintype "passive"))
      (node (ref "TR3") (pin "P$1_TIP") (pinfunction "TIP_P$1_TIP") (pintype "passive"))
    )
    (net (code "76") (name "Net-(TR4-TIP)") (class "Default")
      (node (ref "R15") (pin "2") (pinfunction "2_2") (pintype "passive"))
      (node (ref "TR4") (pin "P$1_TIP") (pinfunction "TIP_P$1_TIP") (pintype "passive"))
    )
    (net (code "77") (name "VCC") (class "Default")
      (node (ref "C1-10UF") (pin "1") (pinfunction "1_1") (pintype "passive"))
      (node (ref "C5-100N") (pin "1") (pinfunction "1_1") (pintype "passive"))
      (node (ref "C6-100N") (pin "1") (pinfunction "1_1") (pintype "passive"))
      (node (ref "D1") (pin "C") (pinfunction "C_C") (pintype "passive"))
      (node (ref "TL074CN-1") (pin "4") (pinfunction "VCC+_4") (pintype "power_in"))
      (node (ref "TL074CN-2") (pin "4") (pinfunction "VCC+_4") (pintype "power_in"))
      (node (ref "U$2") (pin "IN") (pinfunction "IN_IN") (pintype "input"))
    )
    (net (code "78") (name "VSS") (class "Default")
      (node (ref "C7-100N") (pin "1") (pinfunction "1_1") (pintype "passive"))
      (node (ref "C8-100N") (pin "1") (pinfunction "1_1") (pintype "passive"))
      (node (ref "D2") (pin "A") (pinfunction "A_A") (pintype "passive"))
      (node (ref "TL074CN-1") (pin "11") (pinfunction "VCC-_11") (pintype "power_in"))
      (node (ref "TL074CN-2") (pin "11") (pinfunction "VCC-_11") (pintype "power_in"))
    )
    (net (code "79") (name "unconnected-(CV1-SWITCH-PadP$2_SWITCH)") (class "Default")
      (node (ref "CV1") (pin "P$2_SWITCH") (pinfunction "SWITCH_P$2_SWITCH") (pintype "passive"))
    )
    (net (code "80") (name "unconnected-(CV2-SWITCH-PadP$2_SWITCH)") (class "Default")
      (node (ref "CV2") (pin "P$2_SWITCH") (pinfunction "SWITCH_P$2_SWITCH") (pintype "passive"))
    )
    (net (code "81") (name "unconnected-(CV3-SWITCH-PadP$2_SWITCH)") (class "Default")
      (node (ref "CV3") (pin "P$2_SWITCH") (pinfunction "SWITCH_P$2_SWITCH") (pintype "passive"))
    )
    (net (code "82") (name "unconnected-(CV4-SWITCH-PadP$2_SWITCH)") (class "Default")
      (node (ref "CV4") (pin "P$2_SWITCH") (pinfunction "SWITCH_P$2_SWITCH") (pintype "passive"))
    )
    (net (code "83") (name "unconnected-(MCP4922-1-NC-Pad7)") (class "Default")
      (node (ref "MCP4922-1") (pin "7") (pinfunction "NC_7") (pintype "no_connect"))
    )
    (net (code "84") (name "unconnected-(MCP4922-1-NC_2-Pad2)") (class "Default")
      (node (ref "MCP4922-1") (pin "2") (pinfunction "NC_2_2") (pintype "no_connect"))
    )
    (net (code "85") (name "unconnected-(MCP4922-1-NC_3-Pad6)") (class "Default")
      (node (ref "MCP4922-1") (pin "6") (pinfunction "NC_3_6") (pintype "no_connect"))
    )
    (net (code "86") (name "unconnected-(MCP4922-2-NC-Pad7)") (class "Default")
      (node (ref "MCP4922-2") (pin "7") (pinfunction "NC_7") (pintype "no_connect"))
    )
    (net (code "87") (name "unconnected-(MCP4922-2-NC_2-Pad2)") (class "Default")
      (node (ref "MCP4922-2") (pin "2") (pinfunction "NC_2_2") (pintype "no_connect"))
    )
    (net (code "88") (name "unconnected-(MCP4922-2-NC_3-Pad6)") (class "Default")
      (node (ref "MCP4922-2") (pin "6") (pinfunction "NC_3_6") (pintype "no_connect"))
    )
    (net (code "89") (name "unconnected-(TR1-SWITCH-PadP$2_SWITCH)") (class "Default")
      (node (ref "TR1") (pin "P$2_SWITCH") (pinfunction "SWITCH_P$2_SWITCH") (pintype "passive"))
    )
    (net (code "90") (name "unconnected-(TR2-SWITCH-PadP$2_SWITCH)") (class "Default")
      (node (ref "TR2") (pin "P$2_SWITCH") (pinfunction "SWITCH_P$2_SWITCH") (pintype "passive"))
    )
    (net (code "91") (name "unconnected-(TR3-SWITCH-PadP$2_SWITCH)") (class "Default")
      (node (ref "TR3") (pin "P$2_SWITCH") (pinfunction "SWITCH_P$2_SWITCH") (pintype "passive"))
    )
    (net (code "92") (name "unconnected-(TR4-SWITCH-PadP$2_SWITCH)") (class "Default")
      (node (ref "TR4") (pin "P$2_SWITCH") (pinfunction "SWITCH_P$2_SWITCH") (pintype "passive"))
    )
    (net (code "93") (name "unconnected-(U$1-A21{slash}DAC0-Pad21{slash}DAC0)") (class "Default")
      (node (ref "U$1") (pin "21/DAC0") (pinfunction "A21/DAC0_21/DAC0") (pintype "bidirectional"))
    )
    (net (code "94") (name "unconnected-(U$1-Pad3V3)") (class "Default")
      (node (ref "U$1") (pin "3V3") (pinfunction "3V3_3V3") (pintype "bidirectional"))
    )
    (net (code "95") (name "unconnected-(U$1-Pad12{slash}MISO)") (class "Default")
      (node (ref "U$1") (pin "12/MISO") (pinfunction "12/MISO_12/MISO") (pintype "bidirectional"))
    )
    (net (code "96") (name "unconnected-(U$1-Pad32{slash}A13)") (class "Default")
      (node (ref "U$1") (pin "32/A13") (pinfunction "32/A13_32/A13") (pintype "bidirectional"))
    )
    (net (code "97") (name "unconnected-(U$1-Pad33{slash}A14)") (class "Default")
      (node (ref "U$1") (pin "33/A14") (pinfunction "33/A14_33/A14") (pintype "bidirectional"))
    )
    (net (code "98") (name "unconnected-(U$1-Pad34{slash}A15)") (class "Default")
      (node (ref "U$1") (pin "34/A15") (pinfunction "34/A15_34/A15") (pintype "bidirectional"))
    )
    (net (code "99") (name "unconnected-(U$1-Pad35{slash}A16)") (class "Default")
      (node (ref "U$1") (pin "35/A16") (pinfunction "35/A16_35/A16") (pintype "bidirectional"))
    )
    (net (code "100") (name "unconnected-(U$1-Pad36{slash}A17)") (class "Default")
      (node (ref "U$1") (pin "36/A17") (pinfunction "36/A17_36/A17") (pintype "bidirectional"))
    )
    (net (code "101") (name "unconnected-(U$1-Pad37{slash}A18)") (class "Default")
      (node (ref "U$1") (pin "37/A18") (pinfunction "37/A18_37/A18") (pintype "bidirectional"))
    )
    (net (code "102") (name "unconnected-(U$1-Pad38{slash}A19)") (class "Default")
      (node (ref "U$1") (pin "38/A19") (pinfunction "38/A19_38/A19") (pintype "bidirectional"))
    )
    (net (code "103") (name "unconnected-(U$1-Pad39{slash}A20)") (class "Default")
      (node (ref "U$1") (pin "39/A20") (pinfunction "39/A20_39/A20") (pintype "bidirectional"))
    )
    (net (code "104") (name "unconnected-(U$1-PadA10)") (class "Default")
      (node (ref "U$1") (pin "A10") (pinfunction "A10_A10") (pintype "bidirectional"))
    )
    (net (code "105") (name "unconnected-(U$1-PadA11)") (class "Default")
      (node (ref "U$1") (pin "A11") (pinfunction "A11_A11") (pintype "bidirectional"))
    )
    (net (code "106") (name "unconnected-(U$1-PadA22{slash}DAC1)") (class "Default")
      (node (ref "U$1") (pin "A22/DAC1") (pinfunction "A22/DAC1_A22/DAC1") (pintype "bidirectional"))
    )
    (net (code "107") (name "unconnected-(U$1-PadAREF)") (class "Default")
      (node (ref "U$1") (pin "AREF") (pinfunction "AREF_AREF") (pintype "bidirectional"))
    )
    (net (code "108") (name "unconnected-(U$1-PadVUSB)") (class "Default")
      (node (ref "U$1") (pin "VUSB") (pinfunction "VUSB_VUSB") (pintype "bidirectional"))
    )
    (net (code "109") (name "unconnected-(U$4-PadINT)") (class "Default")
      (node (ref "U$4") (pin "INT") (pinfunction "INT_INT") (pintype "bidirectional"))
    )
  )
)
